# WLR089U0_Base.net
KiCad netlist of a schematic drawn in EAGLE
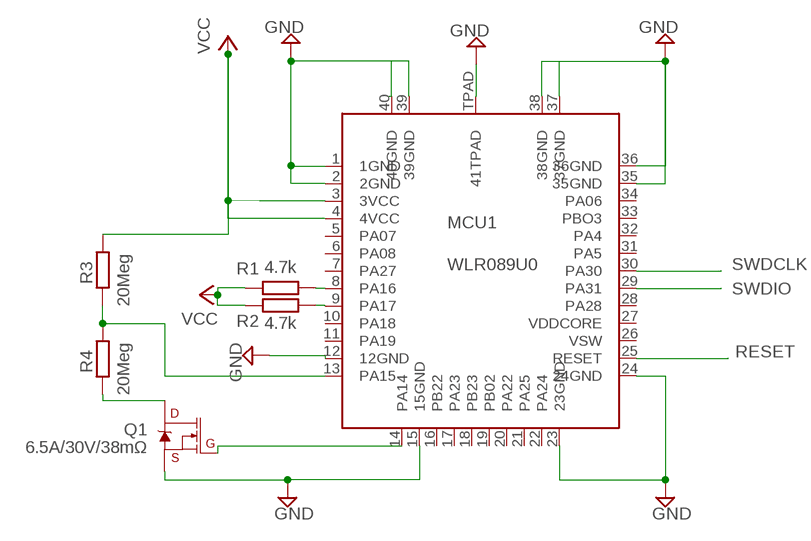
[diagram p0: schematic, sheet 1]

(export (version "E")
  (design (tool "Eeschema 10.0.6"))
  (components
    (comp (ref "MCU1")
      (value "WLR089U0")
      (footprint "eagle-import:WLR089U0")
      (libsource (lib "eagle-import") (part "WLR089U0"))
    )
    (comp (ref "Q1")
      (value "6.5A/30V/38mΩ")
      (footprint "eagle-import:SO08")
      (libsource (lib "eagle-import") (part "MOSFET-NCH-FDS6630A"))
    )
    (comp (ref "R1")
      (value "4.7k")
      (footprint "eagle-import:SMK")
      (libsource (lib "eagle-import") (part "SMK"))
    )
    (comp (ref "R2")
      (value "4.7k")
      (footprint "eagle-import:SMK")
      (libsource (lib "eagle-import") (part "SMK"))
    )
    (comp (ref "R3")
      (value "20Meg")
      (footprint "eagle-import:SMK")
      (libsource (lib "eagle-import") (part "SMK"))
    )
    (comp (ref "R4")
      (value "20Meg")
      (footprint "eagle-import:SMK")
      (libsource (lib "eagle-import") (part "SMK"))
    )
  )
  (nets
    (net (code "1") (name "/RESET") (class "Default")
      (node (ref "MCU1") (pin "25") (pinfunction "RESET_25") (pintype "bidirectional"))
    )
    (net (code "2") (name "/SWDCLK") (class "Default")
      (node (ref "MCU1") (pin "30") (pinfunction "PA30_30") (pintype "bidirectional"))
    )
    (net (code "3") (name "/SWDIO") (class "Default")
      (node (ref "MCU1") (pin "29") (pinfunction "PA31_29") (pintype "bidirectional"))
    )
    (net (code "4") (name "GND") (class "Default")
      (node (ref "MCU1") (pin "1") (pinfunction "1GND_1") (pintype "bidirectional"))
      (node (ref "MCU1") (pin "12") (pinfunction "12GND_12") (pintype "bidirectional"))
      (node (ref "MCU1") (pin "15") (pinfunction "15GND_15") (pintype "bidirectional"))
      (node (ref "MCU1") (pin "2") (pinfunction "2GND_2") (pintype "bidirectional"))
      (node (ref "MCU1") (pin "23") (pinfunction "23GND_23") (pintype "bidirectional"))
      (node (ref "MCU1") (pin "24") (pinfunction "24GND_24") (pintype "bidirectional"))
      (node (ref "MCU1") (pin "35") (pinfunction "35GND_35") (pintype "bidirectional"))
      (node (ref "MCU1") (pin "36") (pinfunction "36GND_36") (pintype "bidirectional"))
      (node (ref "MCU1") (pin "37") (pinfunction "37GND_37") (pintype "bidirectional"))
      (node (ref "MCU1") (pin "38") (pinfunction "38GND_38") (pintype "bidirectional"))
      (node (ref "MCU1") (pin "39") (pinfunction "39GND_39") (pintype "bidirectional"))
      (node (ref "MCU1") (pin "40") (pinfunction "40GND_40") (pintype "bidirectional"))
      (node (ref "MCU1") (pin "TPAD") (pinfunction "41TPAD_TPAD") (pintype "bidirectional"))
      (node (ref "Q1") (pin "1") (pinfunction "S_1") (pintype "bidirectional"))
      (node (ref "Q1") (pin "2") (pinfunction "S_2") (pintype "bidirectional"))
      (node (ref "Q1") (pin "3") (pinfunction "S_3") (pintype "bidirectional"))
    )
    (net (code "5") (name "Net-(MCU1-PA14)") (class "Default")
      (node (ref "MCU1") (pin "14") (pinfunction "PA14_14") (pintype "bidirectional"))
      (node (ref "Q1") (pin "4") (pinfunction "G_4") (pintype "bidirectional"))
    )
    (net (code "6") (name "Net-(MCU1-PA15)") (class "Default")
      (node (ref "MCU1") (pin "13") (pinfunction "PA15_13") (pintype "bidirectional"))
      (node (ref "R3") (pin "1") (pinfunction "1_1") (pintype "passive"))
      (node (ref "R4") (pin "2") (pinfunction "2_2") (pintype "passive"))
    )
    (net (code "7") (name "Net-(MCU1-PA16)") (class "Default")
      (node (ref "MCU1") (pin "8") (pinfunction "PA16_8") (pintype "bidirectional"))
      (node (ref "R1") (pin "1") (pinfunction "1_1") (pintype "passive"))
    )
    (net (code "8") (name "Net-(MCU1-PA17)") (class "Default")
      (node (ref "MCU1") (pin "9") (pinfunction "PA17_9") (pintype "bidirectional"))
      (node (ref "R2") (pin "1") (pinfunction "1_1") (pintype "passive"))
    )
    (net (code "9") (name "Net-(Q1-D-Pad5)") (class "Default")
      (node (ref "Q1") (pin "5") (pinfunction "D_5") (pintype "bidirectional"))
      (node (ref "Q1") (pin "6") (pinfunction "D_6") (pintype "bidirectional"))
      (node (ref "Q1") (pin "7") (pinfunction "D_7") (pintype "bidirectional"))
      (node (ref "Q1") (pin "8") (pinfunction "D_8") (pintype "bidirectional"))
      (node (ref "R4") (pin "1") (pinfunction "1_1") (pintype "passive"))
    )
    (net (code "10") (name "VCC") (class "Default")
      (node (ref "MCU1") (pin "3") (pinfunction "3VCC_3") (pintype "bidirectional"))
      (node (ref "MCU1") (pin "4") (pinfunction "4VCC_4") (pintype "bidirectional"))
      (node (ref "R1") (pin "2") (pinfunction "2_2") (pintype "passive"))
      (node (ref "R2") (pin "2") (pinfunction "2_2") (pintype "passive"))
      (node (ref "R3") (pin "2") (pinfunction "2_2") (pintype "passive"))
    )
    (net (code "11") (name "unconnected-(MCU1-PA4-Pad32)") (class "Default")
      (node (ref "MCU1") (pin "32") (pinfunction "PA4_32") (pintype "bidirectional"))
    )
    (net (code "12") (name "unconnected-(MCU1-PA5-Pad31)") (class "Default")
      (node (ref "MCU1") (pin "31") (pinfunction "PA5_31") (pintype "bidirectional"))
    )
    (net (code "13") (name "unconnected-(MCU1-PA06-Pad34)") (class "Default")
      (node (ref "MCU1") (pin "34") (pinfunction "PA06_34") (pintype "bidirectional"))
    )
    (net (code "14") (name "unconnected-(MCU1-PA07-Pad5)") (class "Default")
      (node (ref "MCU1") (pin "5") (pinfunction "PA07_5") (pintype "bidirectional"))
    )
    (net (code "15") (name "unconnected-(MCU1-PA08-Pad6)") (class "Default")
      (node (ref "MCU1") (pin "6") (pinfunction "PA08_6") (pintype "bidirectional"))
    )
    (net (code "16") (name "unconnected-(MCU1-PA18-Pad10)") (class "Default")
      (node (ref "MCU1") (pin "10") (pinfunction "PA18_10") (pintype "bidirectional"))
    )
    (net (code "17") (name "unconnected-(MCU1-PA19-Pad11)") (class "Default")
      (node (ref "MCU1") (pin "11") (pinfunction "PA19_11") (pintype "bidirectional"))
    )
    (net (code "18") (name "unconnected-(MCU1-PA22-Pad20)") (class "Default")
      (node (ref "MCU1") (pin "20") (pinfunction "PA22_20") (pintype "bidirectional"))
    )
    (net (code "19") (name "unconnected-(MCU1-PA23-Pad17)") (class "Default")
      (node (ref "MCU1") (pin "17") (pinfunction "PA23_17") (pintype "bidirectional"))
    )
    (net (code "20") (name "unconnected-(MCU1-PA24-Pad22)") (class "Default")
      (node (ref "MCU1") (pin "22") (pinfunction "PA24_22") (pintype "bidirectional"))
    )
    (net (code "21") (name "unconnected-(MCU1-PA25-Pad21)") (class "Default")
      (node (ref "MCU1") (pin "21") (pinfunction "PA25_21") (pintype "bidirectional"))
    )
    (net (code "22") (name "unconnected-(MCU1-PA27-Pad7)") (class "Default")
      (node (ref "MCU1") (pin "7") (pinfunction "PA27_7") (pintype "bidirectional"))
    )
    (net (code "23") (name "unconnected-(MCU1-PA28-Pad28)") (class "Default")
      (node (ref "MCU1") (pin "28") (pinfunction "PA28_28") (pintype "bidirectional"))
    )
    (net (code "24") (name "unconnected-(MCU1-PB02-Pad19)") (class "Default")
      (node (ref "MCU1") (pin "19") (pinfunction "PB02_19") (pintype "bidirectional"))
    )
    (net (code "25") (name "unconnected-(MCU1-PB22-Pad16)") (class "Default")
      (node (ref "MCU1") (pin "16") (pinfunction "PB22_16") (pintype "bidirectional"))
    )
    (net (code "26") (name "unconnected-(MCU1-PB23-Pad18)") (class "Default")
      (node (ref "MCU1") (pin "18") (pinfunction "PB23_18") (pintype "bidirectional"))
    )
    (net (code "27") (name "unconnected-(MCU1-PBO3-Pad33)") (class "Default")
      (node (ref "MCU1") (pin "33") (pinfunction "PBO3_33") (pintype "bidirectional"))
    )
    (net (code "28") (name "unconnected-(MCU1-VDDCORE-Pad27)") (class "Default")
      (node (ref "MCU1") (pin "27") (pinfunction "VDDCORE_27") (pintype "bidirectional"))
    )
    (net (code "29") (name "unconnected-(MCU1-VSW-Pad26)") (class "Default")
      (node (ref "MCU1") (pin "26") (pinfunction "VSW_26") (pintype "bidirectional"))
    )
  )
)
